# ArduiNode.net
KiCad netlist of a schematic drawn in EAGLE
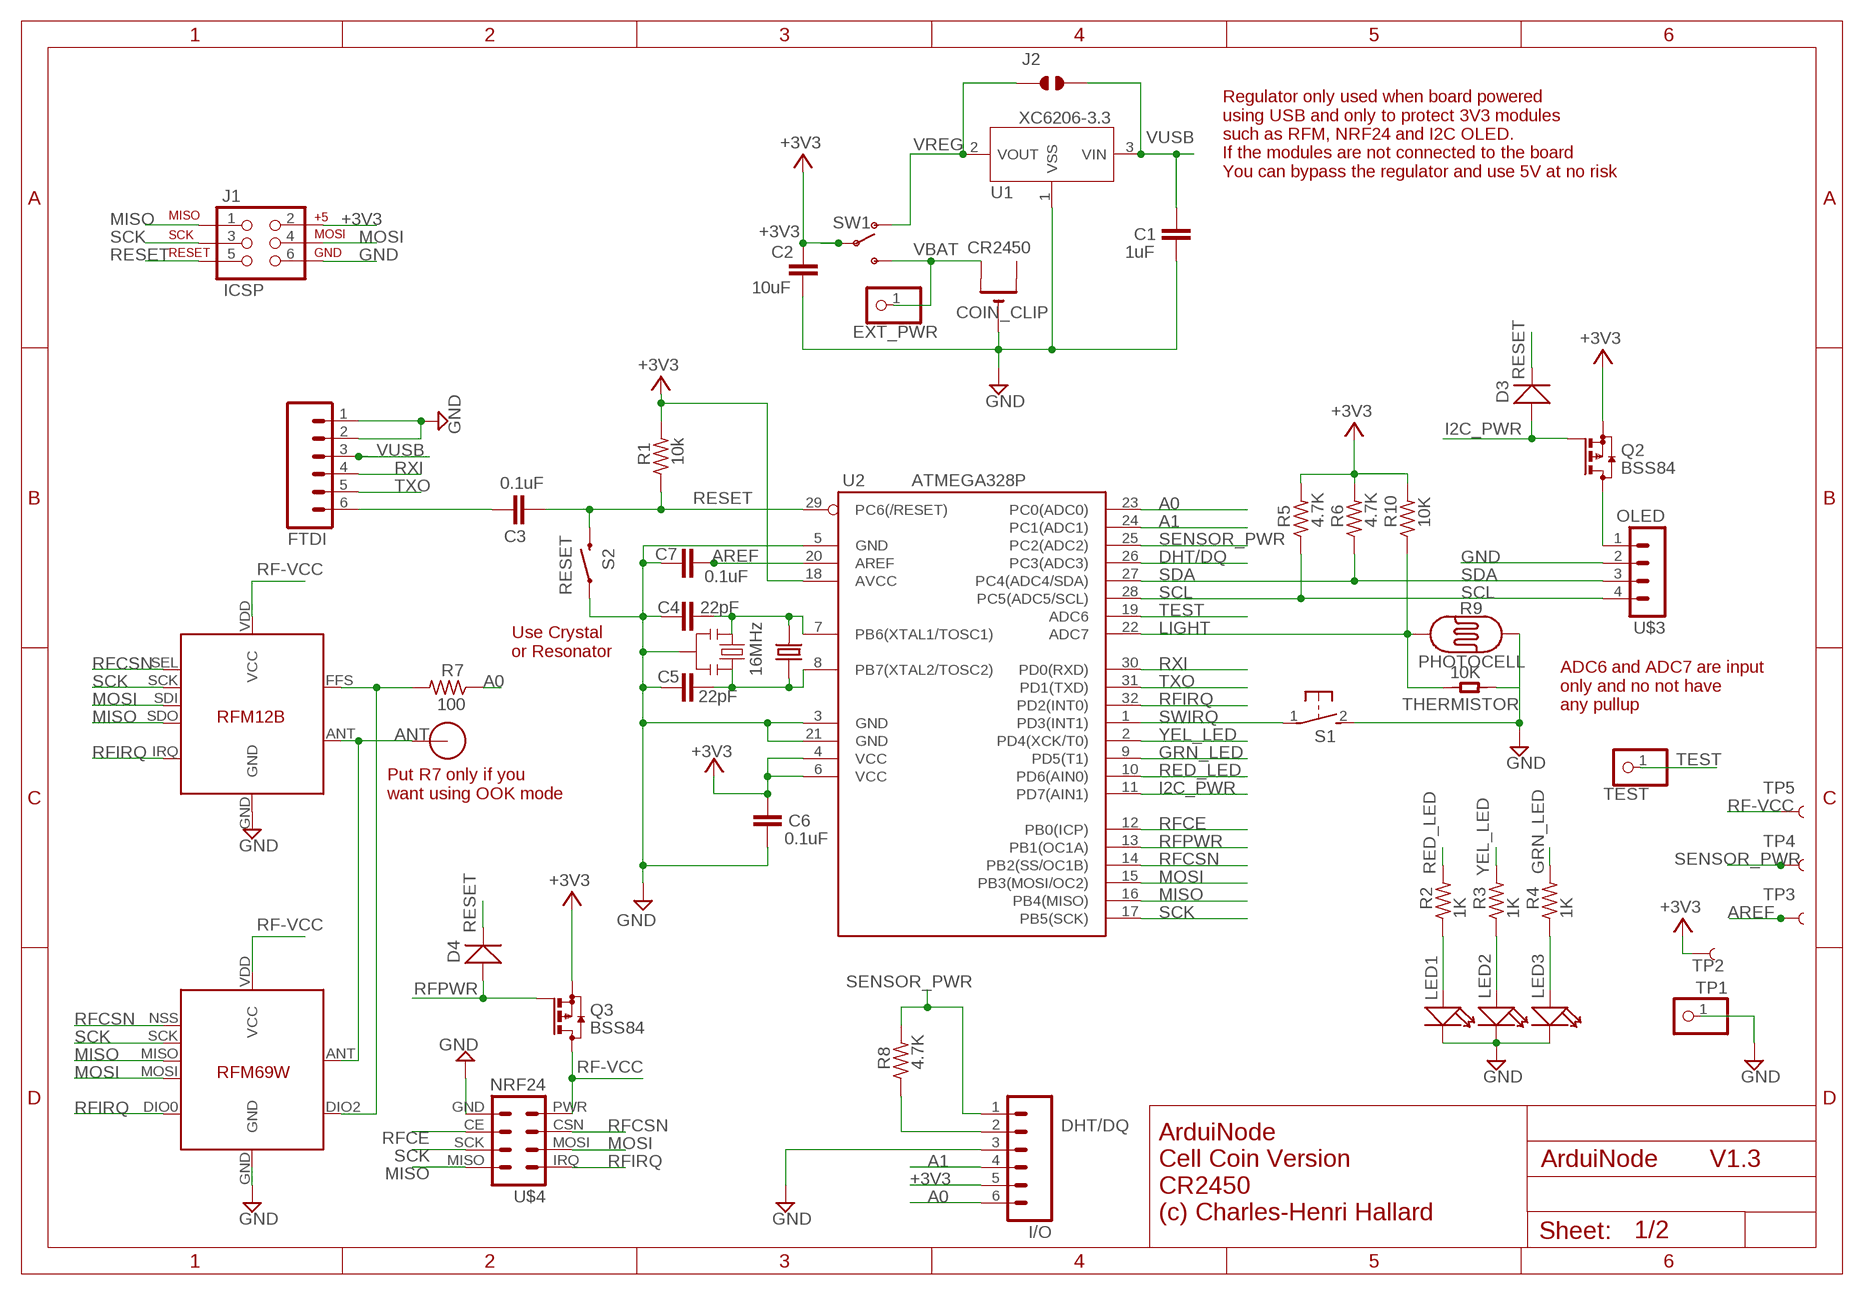
[diagram p0: schematic, sheet 1]
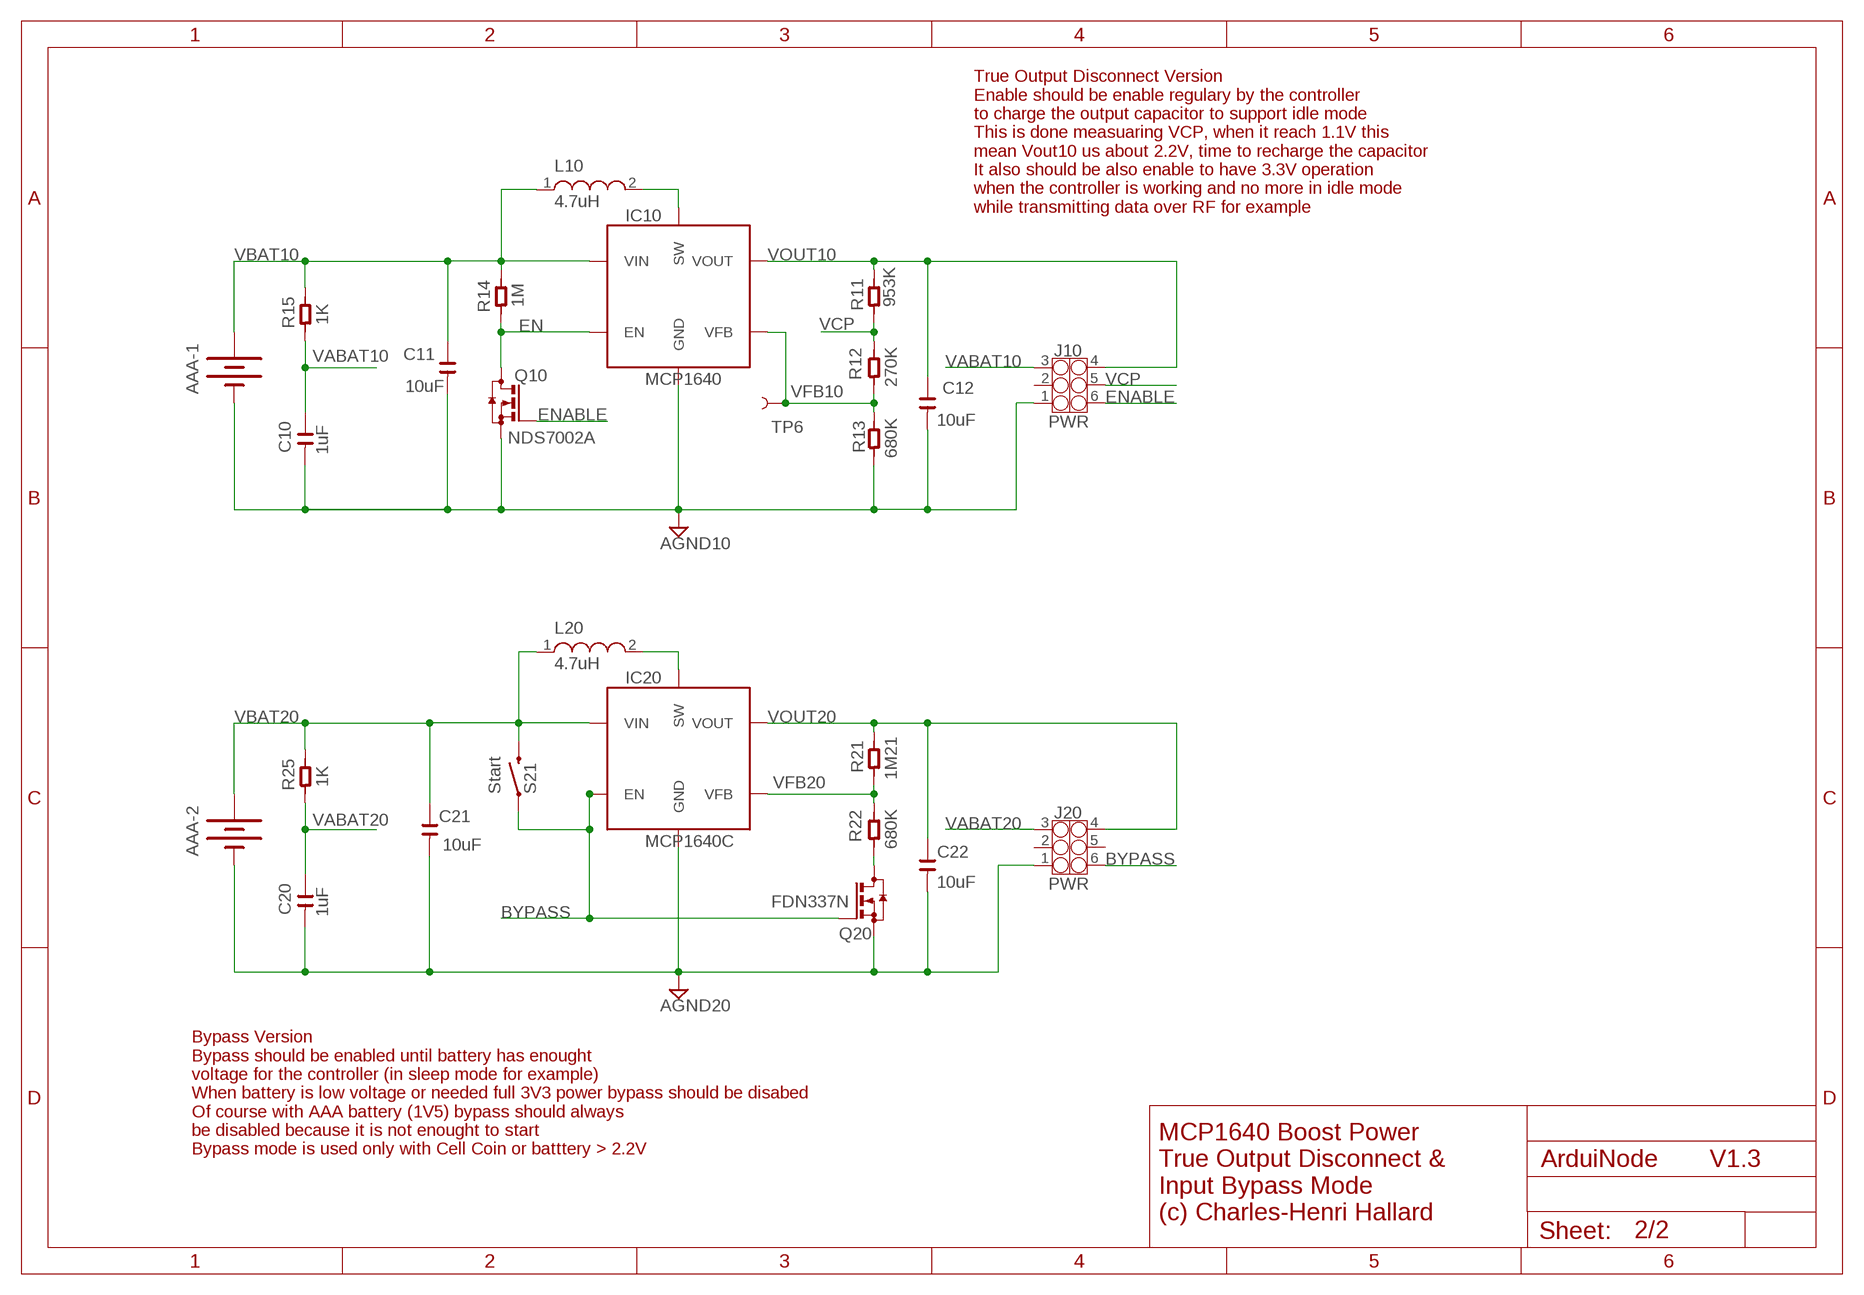
[diagram p1: schematic, sheet 2]

(export (version "E")
  (design (tool "Eeschema 10.0.6"))
  (components
    (comp (ref "AAA-1")
      (value "BATTERYAAA-JL")
      (footprint "eagle-import:BATTERY-AAA-JL")
      (libsource (lib "eagle-import") (part "BATTERYAAA-JL"))
    )
    (comp (ref "AAA-2")
      (value "BATTERYAAA-JL")
      (footprint "eagle-import:BATTERY-AAA-JL")
      (libsource (lib "eagle-import") (part "BATTERYAAA-JL"))
    )
    (comp (ref "C10")
      (value "1uF")
      (footprint "eagle-import:C0805")
      (libsource (lib "eagle-import") (part "C-0805"))
    )
    (comp (ref "C11")
      (value "10uF")
      (footprint "eagle-import:C0805")
      (libsource (lib "eagle-import") (part "C-0805"))
    )
    (comp (ref "C12")
      (value "10uF")
      (footprint "eagle-import:C0805")
      (libsource (lib "eagle-import") (part "C-0805"))
    )
    (comp (ref "C20")
      (value "1uF")
      (footprint "eagle-import:C0805")
      (libsource (lib "eagle-import") (part "C-0805"))
    )
    (comp (ref "C21")
      (value "10uF")
      (footprint "eagle-import:C0805")
      (libsource (lib "eagle-import") (part "C-0805"))
    )
    (comp (ref "C22")
      (value "10uF")
      (footprint "eagle-import:C0805")
      (libsource (lib "eagle-import") (part "C-0805"))
    )
    (comp (ref "IC10")
      (value "MCP1640")
      (footprint "eagle-import:SOT23-6")
      (libsource (lib "eagle-import") (part "MCP1640"))
    )
    (comp (ref "IC20")
      (value "MCP1640C")
      (footprint "eagle-import:SOT23-6")
      (libsource (lib "eagle-import") (part "MCP1640"))
    )
    (comp (ref "J10")
      (value "PWR")
      (footprint "eagle-import:2X3P-2.54-2.54-11.6-3.0-BLACK-MALE")
      (libsource (lib "eagle-import") (part "CONNECTOR-HEADER-2X3P-3460180P1"))
    )
    (comp (ref "J20")
      (value "PWR")
      (footprint "eagle-import:2X3P-2.54-2.54-11.6-3.0-BLACK-MALE")
      (libsource (lib "eagle-import") (part "CONNECTOR-HEADER-2X3P-3460180P1"))
    )
    (comp (ref "L10")
      (value "4.7uH")
      (footprint "eagle-import:L1812")
      (libsource (lib "eagle-import") (part "INDUCTOR-L1812"))
    )
    (comp (ref "L20")
      (value "4.7uH")
      (footprint "eagle-import:L1812")
      (libsource (lib "eagle-import") (part "INDUCTOR-L1812"))
    )
    (comp (ref "Q10")
      (value "NDS7002A")
      (footprint "eagle-import:SOT23")
      (libsource (lib "eagle-import") (part "BSS123"))
    )
    (comp (ref "Q20")
      (value "FDN337N")
      (footprint "eagle-import:SOT23")
      (libsource (lib "eagle-import") (part "BSS123"))
    )
    (comp (ref "R11")
      (value "953K")
      (footprint "eagle-import:R0603")
      (libsource (lib "eagle-import") (part "R-0603"))
    )
    (comp (ref "R12")
      (value "270K")
      (footprint "eagle-import:R0603")
      (libsource (lib "eagle-import") (part "R-0603"))
    )
    (comp (ref "R13")
      (value "680K")
      (footprint "eagle-import:R0603")
      (libsource (lib "eagle-import") (part "R-0603"))
    )
    (comp (ref "R14")
      (value "1M")
      (footprint "eagle-import:R0603")
      (libsource (lib "eagle-import") (part "R-0603"))
    )
    (comp (ref "R15")
      (value "1K")
      (footprint "eagle-import:R0603")
      (libsource (lib "eagle-import") (part "R-0603"))
    )
    (comp (ref "R21")
      (value "1M21")
      (footprint "eagle-import:R0603")
      (libsource (lib "eagle-import") (part "R-0603"))
    )
    (comp (ref "R22")
      (value "680K")
      (footprint "eagle-import:R0603")
      (libsource (lib "eagle-import") (part "R-0603"))
    )
    (comp (ref "R25")
      (value "1K")
      (footprint "eagle-import:R0603")
      (libsource (lib "eagle-import") (part "R-0603"))
    )
    (comp (ref "S21")
      (value "Start")
      (footprint "eagle-import:TACTILE-SWITCH-1101NE")
      (libsource (lib "eagle-import") (part "SWITCH-MOMENTARY-2-SMD-1101NE"))
    )
    (comp (ref "TP6")
      (value "TEST-POINT3")
      (footprint "eagle-import:PAD.03X.03")
      (libsource (lib "eagle-import") (part "TEST-POINT3"))
    )
    (comp (ref "C1")
      (value "1uF")
      (footprint "eagle-import:C0805K")
      (libsource (lib "eagle-import") (part "C-EUC0805K"))
    )
    (comp (ref "C2")
      (value "10uF")
      (footprint "eagle-import:C0805K")
      (libsource (lib "eagle-import") (part "C-EUC0805K"))
    )
    (comp (ref "C3")
      (value "0.1uF")
      (footprint "eagle-import:C0805K")
      (libsource (lib "eagle-import") (part "C-EUC0805K"))
    )
    (comp (ref "C4")
      (value "22pF")
      (footprint "eagle-import:C0805K")
      (libsource (lib "eagle-import") (part "C-EUC0805K"))
    )
    (comp (ref "C5")
      (value "22pF")
      (footprint "eagle-import:C0805K")
      (libsource (lib "eagle-import") (part "C-EUC0805K"))
    )
    (comp (ref "C6")
      (value "0.1uF")
      (footprint "eagle-import:C0805K")
      (libsource (lib "eagle-import") (part "C-EUC0805K"))
    )
    (comp (ref "C7")
      (value "0.1uF")
      (footprint "eagle-import:C0805K")
      (libsource (lib "eagle-import") (part "C-EUC0805K"))
    )
    (comp (ref "COIN_CLIP")
      (value "CR2450")
      (footprint "eagle-import:CR1220-THM")
      (libsource (lib "eagle-import") (part "CR2450CR2450-THM"))
    )
    (comp (ref "D3")
      (value "D-SOD-123")
      (footprint "eagle-import:SOD123")
      (libsource (lib "eagle-import") (part "D-SOD-123"))
    )
    (comp (ref "D4")
      (value "D-SOD-123")
      (footprint "eagle-import:SOD123")
      (libsource (lib "eagle-import") (part "D-SOD-123"))
    )
    (comp (ref "EXT_PWR")
      (value "PINHD-1X1CB")
      (footprint "eagle-import:1X01-CLEANBIG")
      (libsource (lib "eagle-import") (part "PINHD-1X1CB"))
    )
    (comp (ref "FTDI")
      (value "M06SIP_LOCK")
      (footprint "eagle-import:1X06-SIP_LOCK")
      (libsource (lib "eagle-import") (part "M06SIP_LOCK"))
    )
    (comp (ref "I/O")
      (value "M06FEMALE_LOCK")
      (footprint "eagle-import:1X06_FEMALE_LOCK.010")
      (libsource (lib "eagle-import") (part "M06FEMALE_LOCK"))
    )
    (comp (ref "J1")
      (value "ICSP")
      (footprint "eagle-import:2X3_LOCK")
      (libsource (lib "eagle-import") (part "AVR_SPI_PRG_62X3_LOCK"))
    )
    (comp (ref "J2")
      (value "JUMPER_SOLDER_1X2")
      (footprint "eagle-import:JUMPER_SOLDER_1X2")
      (libsource (lib "eagle-import") (part "JUMPER_SOLDER_1X2"))
    )
    (comp (ref "LED1")
      (value "LED0805")
      (footprint "eagle-import:LED-0805")
      (libsource (lib "eagle-import") (part "LED0805"))
    )
    (comp (ref "LED2")
      (value "LED0805")
      (footprint "eagle-import:LED-0805")
      (libsource (lib "eagle-import") (part "LED0805"))
    )
    (comp (ref "LED3")
      (value "LED0805")
      (footprint "eagle-import:LED-0805")
      (libsource (lib "eagle-import") (part "LED0805"))
    )
    (comp (ref "Q2")
      (value "BSS84")
      (footprint "eagle-import:SOT23")
      (libsource (lib "eagle-import") (part "BSS84"))
    )
    (comp (ref "Q3")
      (value "BSS84")
      (footprint "eagle-import:SOT23")
      (libsource (lib "eagle-import") (part "BSS84"))
    )
    (comp (ref "R1")
      (value "10k")
      (footprint "eagle-import:M0805")
      (libsource (lib "eagle-import") (part "R-US_M0805"))
    )
    (comp (ref "R2")
      (value "1K")
      (footprint "eagle-import:M0805")
      (libsource (lib "eagle-import") (part "R-US_M0805"))
    )
    (comp (ref "R3")
      (value "1K")
      (footprint "eagle-import:M0805")
      (libsource (lib "eagle-import") (part "R-US_M0805"))
    )
    (comp (ref "R4")
      (value "1K")
      (footprint "eagle-import:M0805")
      (libsource (lib "eagle-import") (part "R-US_M0805"))
    )
    (comp (ref "R5")
      (value "4.7K")
      (footprint "eagle-import:M0805")
      (libsource (lib "eagle-import") (part "R-US_M0805"))
    )
    (comp (ref "R6")
      (value "4.7K")
      (footprint "eagle-import:M0805")
      (libsource (lib "eagle-import") (part "R-US_M0805"))
    )
    (comp (ref "R7")
      (value "100")
      (footprint "eagle-import:M0805")
      (libsource (lib "eagle-import") (part "R-US_M0805"))
    )
    (comp (ref "R8")
      (value "4.7K")
      (footprint "eagle-import:M0805")
      (libsource (lib "eagle-import") (part "R-US_M0805"))
    )
    (comp (ref "R9")
      (value "PHOTOCELL")
      (footprint "eagle-import:PHOTOCELL")
      (libsource (lib "eagle-import") (part "PHOTOCELLPTH"))
    )
    (comp (ref "R10")
      (value "10K")
      (footprint "eagle-import:M0805")
      (libsource (lib "eagle-import") (part "R-US_M0805"))
    )
    (comp (ref "RFM12B")
      (value "RFM12BNO")
      (footprint "eagle-import:RFM12B")
      (libsource (lib "eagle-import") (part "RFM12BNO"))
    )
    (comp (ref "S1")
      (value "DTS-3")
      (footprint "eagle-import:DTS-3")
      (libsource (lib "eagle-import") (part "DTS-3"))
    )
    (comp (ref "S2")
      (value "RESET")
      (footprint "eagle-import:TACTILE-SWITCH-1101NE")
      (libsource (lib "eagle-import") (part "SWITCH-MOMENTARY-2-SMD-1101NE"))
    )
    (comp (ref "SW1")
      (value "USB_COIN")
      (footprint "eagle-import:SWITCH-SPDT-SMD")
      (libsource (lib "eagle-import") (part "SW_SPDT_SMD"))
    )
    (comp (ref "TEST")
      (value "PINHD-1X1CB")
      (footprint "eagle-import:1X01-CLEANBIG")
      (libsource (lib "eagle-import") (part "PINHD-1X1CB"))
    )
    (comp (ref "THERMISTOR")
      (value "10K")
      (footprint "eagle-import:R0603")
      (libsource (lib "eagle-import") (part "R-0603"))
    )
    (comp (ref "TP1")
      (value "PINHD-1X1")
      (footprint "eagle-import:1X01")
      (libsource (lib "eagle-import") (part "PINHD-1X1"))
    )
    (comp (ref "TP2")
      (value "TEST-POINT3X5")
      (footprint "eagle-import:PAD.03X.05")
      (libsource (lib "eagle-import") (part "TEST-POINT3X5"))
    )
    (comp (ref "TP3")
      (value "TEST-POINT3X5")
      (footprint "eagle-import:PAD.03X.05")
      (libsource (lib "eagle-import") (part "TEST-POINT3X5"))
    )
    (comp (ref "TP4")
      (value "TEST-POINT3X5")
      (footprint "eagle-import:PAD.03X.05")
      (libsource (lib "eagle-import") (part "TEST-POINT3X5"))
    )
    (comp (ref "TP5")
      (value "TEST-POINT3X5")
      (footprint "eagle-import:PAD.03X.05")
      (libsource (lib "eagle-import") (part "TEST-POINT3X5"))
    )
    (comp (ref "U$3")
      (value "OLED")
      (footprint "eagle-import:1X04_LOCK")
      (libsource (lib "eagle-import") (part "M04_LOCK"))
    )
    (comp (ref "U$4")
      (value "NRF24")
      (footprint "eagle-import:2X04_LOCK")
      (libsource (lib "eagle-import") (part "NRF24"))
    )
    (comp (ref "U$11")
      (value "RFM12B_ANTENNA")
      (footprint "eagle-import:RFM12B-ANTENNA")
      (libsource (lib "eagle-import") (part "RFM12B_ANTENNA"))
    )
    (comp (ref "U1")
      (value "XC6206-3.3")
      (footprint "eagle-import:SOT23")
      (libsource (lib "eagle-import") (part "XC6206-3.3-1300260P1"))
    )
    (comp (ref "U2")
      (value "ATMEGA328P")
      (footprint "eagle-import:TQFP32")
      (libsource (lib "eagle-import") (part "ATMEGA328P-AU-1030060P1"))
    )
    (comp (ref "X2")
      (value "16MHz")
      (footprint "eagle-import:2P-SMD-5.0X3.2")
      (libsource (lib "eagle-import") (part "CRYSTAL-0500290P1"))
    )
    (comp (ref "X3")
      (value "RFM69")
      (footprint "eagle-import:RFM69W-MINPADS")
      (libsource (lib "eagle-import") (part "RFM69"))
    )
    (comp (ref "Y1")
      (value "16MHz")
      (footprint "eagle-import:RESONATOR-SMD")
      (libsource (lib "eagle-import") (part "RESONATOR16MHZ"))
    )
  )
  (nets
    (net (code "1") (name "+3V3") (class "Default")
      (node (ref "C2") (pin "1") (pinfunction "1_1") (pintype "passive"))
      (node (ref "C6") (pin "2") (pinfunction "2_2") (pintype "passive"))
      (node (ref "I/O") (pin "5") (pinfunction "5_5") (pintype "passive"))
      (node (ref "J1") (pin "2") (pinfunction "2_2") (pintype "passive"))
      (node (ref "Q2") (pin "2") (pinfunction "S_2") (pintype "passive"))
      (node (ref "Q3") (pin "2") (pinfunction "S_2") (pintype "passive"))
      (node (ref "R1") (pin "2") (pinfunction "2_2") (pintype "passive"))
      (node (ref "R10") (pin "2") (pinfunction "2_2") (pintype "passive"))
      (node (ref "R5") (pin "2") (pinfunction "2_2") (pintype "passive"))
      (node (ref "R6") (pin "2") (pinfunction "2_2") (pintype "passive"))
      (node (ref "SW1") (pin "2") (pinfunction "2_2") (pintype "passive"))
      (node (ref "TP2") (pin "P$1") (pinfunction "1_P$1") (pintype "bidirectional"))
      (node (ref "U2") (pin "18") (pinfunction "AVCC_18") (pintype "bidirectional"))
      (node (ref "U2") (pin "4") (pinfunction "VCC_4") (pintype "bidirectional"))
      (node (ref "U2") (pin "6") (pinfunction "VCC_6") (pintype "bidirectional"))
    )
    (net (code "2") (name "A0") (class "Default")
      (node (ref "I/O") (pin "6") (pinfunction "6_6") (pintype "passive"))
      (node (ref "R7") (pin "1") (pinfunction "1_1") (pintype "passive"))
      (node (ref "U2") (pin "23") (pinfunction "PC0(ADC0)_23") (pintype "bidirectional"))
    )
    (net (code "3") (name "A1") (class "Default")
      (node (ref "I/O") (pin "4") (pinfunction "4_4") (pintype "passive"))
      (node (ref "U2") (pin "24") (pinfunction "PC1(ADC1)_24") (pintype "bidirectional"))
    )
    (net (code "4") (name "AGND10") (class "Default")
      (node (ref "AAA-1") (pin "GND@1") (pinfunction "-_GND@1") (pintype "power_in"))
      (node (ref "C10") (pin "1") (pinfunction "1_1") (pintype "bidirectional"))
      (node (ref "C11") (pin "1") (pinfunction "1_1") (pintype "bidirectional"))
      (node (ref "C12") (pin "1") (pinfunction "1_1") (pintype "bidirectional"))
      (node (ref "IC10") (pin "2") (pinfunction "GND_2") (pintype "power_in"))
      (node (ref "J10") (pin "1") (pinfunction "1_1") (pintype "bidirectional"))
      (node (ref "Q10") (pin "2") (pinfunction "S_2") (pintype "passive"))
      (node (ref "R13") (pin "1") (pinfunction "1_1") (pintype "bidirectional"))
    )
    (net (code "5") (name "AGND20") (class "Default")
      (node (ref "AAA-2") (pin "GND@1") (pinfunction "-_GND@1") (pintype "power_in"))
      (node (ref "C20") (pin "1") (pinfunction "1_1") (pintype "bidirectional"))
      (node (ref "C21") (pin "1") (pinfunction "1_1") (pintype "bidirectional"))
      (node (ref "C22") (pin "1") (pinfunction "1_1") (pintype "bidirectional"))
      (node (ref "IC20") (pin "2") (pinfunction "GND_2") (pintype "power_in"))
      (node (ref "J20") (pin "1") (pinfunction "1_1") (pintype "bidirectional"))
      (node (ref "Q20") (pin "2") (pinfunction "S_2") (pintype "passive"))
    )
    (net (code "6") (name "ANT") (class "Default")
      (node (ref "RFM12B") (pin "ANT") (pinfunction "ANT_ANT") (pintype "passive"))
      (node (ref "U$11") (pin "P$1") (pinfunction "1_P$1") (pintype "bidirectional"))
      (node (ref "X3") (pin "ANT") (pinfunction "ANT_ANT") (pintype "passive"))
    )
    (net (code "7") (name "AREF") (class "Default")
      (node (ref "C7") (pin "1") (pinfunction "1_1") (pintype "passive"))
      (node (ref "TP3") (pin "P$1") (pinfunction "1_P$1") (pintype "bidirectional"))
      (node (ref "U2") (pin "20") (pinfunction "AREF_20") (pintype "bidirectional"))
    )
    (net (code "8") (name "BYPASS") (class "Default")
      (node (ref "IC20") (pin "3") (pinfunction "EN_3") (pintype "input"))
      (node (ref "J20") (pin "6") (pinfunction "6_6") (pintype "bidirectional"))
      (node (ref "Q20") (pin "1") (pinfunction "G_1") (pintype "passive"))
      (node (ref "S21") (pin "P$1") (pinfunction "1_P$1") (pintype "passive"))
    )
    (net (code "9") (name "DHT{slash}DQ") (class "Default")
      (node (ref "I/O") (pin "2") (pinfunction "2_2") (pintype "passive"))
      (node (ref "R8") (pin "1") (pinfunction "1_1") (pintype "passive"))
      (node (ref "U2") (pin "26") (pinfunction "PC3(ADC3)_26") (pintype "bidirectional"))
    )
    (net (code "10") (name "EN") (class "Default")
      (node (ref "IC10") (pin "3") (pinfunction "EN_3") (pintype "input"))
      (node (ref "Q10") (pin "3") (pinfunction "D_3") (pintype "passive"))
      (node (ref "R14") (pin "1") (pinfunction "1_1") (pintype "bidirectional"))
    )
    (net (code "11") (name "ENABLE") (class "Default")
      (node (ref "J10") (pin "6") (pinfunction "6_6") (pintype "bidirectional"))
      (node (ref "Q10") (pin "1") (pinfunction "G_1") (pintype "passive"))
    )
    (net (code "12") (name "GND") (class "Default")
      (node (ref "C1") (pin "2") (pinfunction "2_2") (pintype "passive"))
      (node (ref "C2") (pin "2") (pinfunction "2_2") (pintype "passive"))
      (node (ref "C4") (pin "2") (pinfunction "2_2") (pintype "passive"))
      (node (ref "C5") (pin "2") (pinfunction "2_2") (pintype "passive"))
      (node (ref "C6") (pin "1") (pinfunction "1_1") (pintype "passive"))
      (node (ref "C7") (pin "2") (pinfunction "2_2") (pintype "passive"))
      (node (ref "COIN_CLIP") (pin "GND") (pinfunction "-_GND") (pintype "passive"))
      (node (ref "FTDI") (pin "1") (pinfunction "1_1") (pintype "passive"))
      (node (ref "FTDI") (pin "2") (pinfunction "2_2") (pintype "passive"))
      (node (ref "I/O") (pin "3") (pinfunction "3_3") (pintype "passive"))
      (node (ref "J1") (pin "6") (pinfunction "6_6") (pintype "passive"))
      (node (ref "LED1") (pin "-") (pinfunction "-_-") (pintype "passive"))
      (node (ref "LED2") (pin "-") (pinfunction "-_-") (pintype "passive"))
      (node (ref "LED3") (pin "-") (pinfunction "-_-") (pintype "passive"))
      (node (ref "R9") (pin "1") (pinfunction "P$1_1") (pintype "bidirectional"))
      (node (ref "RFM12B") (pin "GND") (pinfunction "GND_GND") (pintype "power_in"))
      (node (ref "S1") (pin "2") (pinfunction "2_2") (pintype "passive"))
      (node (ref "S2") (pin "P$1") (pinfunction "1_P$1") (pintype "passive"))
      (node (ref "THERMISTOR") (pin "1") (pinfunction "1_1") (pintype "bidirectional"))
      (node (ref "TP1") (pin "1") (pinfunction "1_1") (pintype "passive"))
      (node (ref "U$3") (pin "2") (pinfunction "2_2") (pintype "passive"))
      (node (ref "U$4") (pin "GND") (pinfunction "GND_GND") (pintype "power_in"))
      (node (ref "U1") (pin "1") (pinfunction "VSS_1") (pintype "power_in"))
      (node (ref "U2") (pin "21") (pinfunction "GND_21") (pintype "bidirectional"))
      (node (ref "U2") (pin "3") (pinfunction "GND_3") (pintype "bidirectional"))
      (node (ref "U2") (pin "5") (pinfunction "GND_5") (pintype "bidirectional"))
      (node (ref "X3") (pin "GND") (pinfunction "GND_GND") (pintype "power_in"))
      (node (ref "Y1") (pin "2") (pinfunction "2_2") (pintype "passive"))
    )
    (net (code "13") (name "GRN_LED") (class "Default")
      (node (ref "R4") (pin "2") (pinfunction "2_2") (pintype "passive"))
      (node (ref "U2") (pin "9") (pinfunction "PD5(T1)_9") (pintype "bidirectional"))
    )
    (net (code "14") (name "I2C_PWR") (class "Default")
      (node (ref "D3") (pin "+") (pinfunction "+_+") (pintype "passive"))
      (node (ref "Q2") (pin "1") (pinfunction "G_1") (pintype "passive"))
      (node (ref "U2") (pin "11") (pinfunction "PD7(AIN1)_11") (pintype "bidirectional"))
    )
    (net (code "15") (name "LIGHT") (class "Default")
      (node (ref "R10") (pin "1") (pinfunction "1_1") (pintype "passive"))
      (node (ref "R9") (pin "2") (pinfunction "P$2_2") (pintype "bidirectional"))
      (node (ref "THERMISTOR") (pin "2") (pinfunction "2_2") (pintype "bidirectional"))
      (node (ref "U2") (pin "22") (pinfunction "ADC7_22") (pintype "bidirectional"))
    )
    (net (code "16") (name "MISO") (class "Default")
      (node (ref "J1") (pin "1") (pinfunction "1_1") (pintype "passive"))
      (node (ref "RFM12B") (pin "SDO") (pinfunction "SDO_SDO") (pintype "output"))
      (node (ref "U$4") (pin "MISO") (pinfunction "MISO_MISO") (pintype "passive"))
      (node (ref "U2") (pin "16") (pinfunction "PB4(MISO)_16") (pintype "bidirectional"))
      (node (ref "X3") (pin "MISO") (pinfunction "MISO_MISO") (pintype "input"))
    )
    (net (code "17") (name "MOSI") (class "Default")
      (node (ref "J1") (pin "4") (pinfunction "4_4") (pintype "passive"))
      (node (ref "RFM12B") (pin "SDI") (pinfunction "SDI_SDI") (pintype "input"))
      (node (ref "U$4") (pin "MOSI") (pinfunction "MOSI_MOSI") (pintype "passive"))
      (node (ref "U2") (pin "15") (pinfunction "PB3(MOSI/OC2)_15") (pintype "bidirectional"))
      (node (ref "X3") (pin "MOSI") (pinfunction "MOSI_MOSI") (pintype "output"))
    )
    (net (code "18") (name "Net-(C3-Pad1)") (class "Default")
      (node (ref "C3") (pin "1") (pinfunction "1_1") (pintype "passive"))
      (node (ref "FTDI") (pin "6") (pinfunction "6_6") (pintype "passive"))
    )
    (net (code "19") (name "Net-(IC10-SW)") (class "Default")
      (node (ref "IC10") (pin "1") (pinfunction "SW_1") (pintype "passive"))
      (node (ref "L10") (pin "2") (pinfunction "2_2") (pintype "passive"))
    )
    (net (code "20") (name "Net-(IC20-SW)") (class "Default")
      (node (ref "IC20") (pin "1") (pinfunction "SW_1") (pintype "passive"))
      (node (ref "L20") (pin "2") (pinfunction "2_2") (pintype "passive"))
    )
    (net (code "21") (name "Net-(LED1-Pad+)") (class "Default")
      (node (ref "LED1") (pin "+") (pinfunction "+_+") (pintype "passive"))
      (node (ref "R2") (pin "1") (pinfunction "1_1") (pintype "passive"))
    )
    (net (code "22") (name "Net-(LED2-Pad+)") (class "Default")
      (node (ref "LED2") (pin "+") (pinfunction "+_+") (pintype "passive"))
      (node (ref "R3") (pin "1") (pinfunction "1_1") (pintype "passive"))
    )
    (net (code "23") (name "Net-(LED3-Pad+)") (class "Default")
      (node (ref "LED3") (pin "+") (pinfunction "+_+") (pintype "passive"))
      (node (ref "R4") (pin "1") (pinfunction "1_1") (pintype "passive"))
    )
    (net (code "24") (name "Net-(Q2-D)") (class "Default")
      (node (ref "Q2") (pin "3") (pinfunction "D_3") (pintype "passive"))
      (node (ref "U$3") (pin "1") (pinfunction "1_1") (pintype "passive"))
    )
    (net (code "25") (name "Net-(Q20-D)") (class "Default")
      (node (ref "Q20") (pin "3") (pinfunction "D_3") (pintype "passive"))
      (node (ref "R22") (pin "1") (pinfunction "1_1") (pintype "bidirectional"))
    )
    (net (code "26") (name "Net-(R7-Pad2)") (class "Default")
      (node (ref "R7") (pin "2") (pinfunction "2_2") (pintype "passive"))
      (node (ref "RFM12B") (pin "FFS") (pinfunction "FFS_FFS") (pintype "bidirectional"))
      (node (ref "X3") (pin "DIO2") (pinfunction "DIO2_DIO2") (pintype "open_collector"))
    )
    (net (code "27") (name "Net-(U2-PB6(XTAL1{slash}TOSC1))") (class "Default")
      (node (ref "C4") (pin "1") (pinfunction "1_1") (pintype "passive"))
      (node (ref "U2") (pin "7") (pinfunction "PB6(XTAL1/TOSC1)_7") (pintype "bidirectional"))
      (node (ref "X2") (pin "2") (pinfunction "2_2") (pintype "passive"))
      (node (ref "Y1") (pin "1") (pinfunction "1_1") (pintype "passive"))
    )
    (net (code "28") (name "Net-(U2-PB7(XTAL2{slash}TOSC2))") (class "Default")
      (node (ref "C5") (pin "1") (pinfunction "1_1") (pintype "passive"))
      (node (ref "U2") (pin "8") (pinfunction "PB7(XTAL2/TOSC2)_8") (pintype "bidirectional"))
      (node (ref "X2") (pin "1") (pinfunction "1_1") (pintype "passive"))
      (node (ref "Y1") (pin "3") (pinfunction "3_3") (pintype "passive"))
    )
    (net (code "29") (name "RED_LED") (class "Default")
      (node (ref "R2") (pin "2") (pinfunction "2_2") (pintype "passive"))
      (node (ref "U2") (pin "10") (pinfunction "PD6(AIN0)_10") (pintype "bidirectional"))
    )
    (net (code "30") (name "RESET") (class "Default")
      (node (ref "C3") (pin "2") (pinfunction "2_2") (pintype "passive"))
      (node (ref "D3") (pin "-") (pinfunction "-_-") (pintype "passive"))
      (node (ref "D4") (pin "-") (pinfunction "-_-") (pintype "passive"))
      (node (ref "J1") (pin "5") (pinfunction "5_5") (pintype "passive"))
      (node (ref "R1") (pin "1") (pinfunction "1_1") (pintype "passive"))
      (node (ref "S2") (pin "P$2") (pinfunction "2_P$2") (pintype "passive"))
      (node (ref "U2") (pin "29") (pinfunction "PC6(/RESET)_29") (pintype "bidirectional"))
    )
    (net (code "31") (name "RF-VCC") (class "Default")
      (node (ref "Q3") (pin "3") (pinfunction "D_3") (pintype "passive"))
      (node (ref "RFM12B") (pin "VDD") (pinfunction "VCC_VDD") (pintype "power_in"))
      (node (ref "TP5") (pin "P$1") (pinfunction "1_P$1") (pintype "bidirectional"))
      (node (ref "U$4") (pin "PWR") (pinfunction "VCC_PWR") (pintype "power_in"))
      (node (ref "X3") (pin "VDD") (pinfunction "VCC_VDD") (pintype "power_in"))
    )
    (net (code "32") (name "RFCE") (class "Default")
      (node (ref "U$4") (pin "CE") (pinfunction "CE_CE") (pintype "passive"))
      (node (ref "U2") (pin "12") (pinfunction "PB0(ICP)_12") (pintype "bidirectional"))
    )
    (net (code "33") (name "RFCSN") (class "Default")
      (node (ref "RFM12B") (pin "SEL") (pinfunction "SEL_SEL") (pintype "input"))
      (node (ref "U$4") (pin "CSN") (pinfunction "CSN_CSN") (pintype "passive"))
      (node (ref "U2") (pin "14") (pinfunction "PB2(SS/OC1B)_14") (pintype "bidirectional"))
      (node (ref "X3") (pin "NSS") (pinfunction "SEL_NSS") (pintype "input"))
    )
    (net (code "34") (name "RFIRQ") (class "Default")
      (node (ref "RFM12B") (pin "IRQ") (pinfunction "IRQ_IRQ") (pintype "open_collector"))
      (node (ref "U$4") (pin "IRQ") (pinfunction "IRQ_IRQ") (pintype "passive"))
      (node (ref "U2") (pin "32") (pinfunction "PD2(INT0)_32") (pintype "bidirectional"))
      (node (ref "X3") (pin "DIO0") (pinfunction "DIO0_DIO0") (pintype "open_collector"))
    )
    (net (code "35") (name "RFPWR") (class "Default")
      (node (ref "D4") (pin "+") (pinfunction "+_+") (pintype "passive"))
      (node (ref "Q3") (pin "1") (pinfunction "G_1") (pintype "passive"))
      (node (ref "U2") (pin "13") (pinfunction "PB1(OC1A)_13") (pintype "bidirectional"))
    )
    (net (code "36") (name "RXI") (class "Default")
      (node (ref "FTDI") (pin "4") (pinfunction "4_4") (pintype "passive"))
      (node (ref "U2") (pin "30") (pinfunction "PD0(RXD)_30") (pintype "bidirectional"))
    )
    (net (code "37") (name "SCK") (class "Default")
      (node (ref "J1") (pin "3") (pinfunction "3_3") (pintype "passive"))
      (node (ref "RFM12B") (pin "SCK") (pinfunction "SCK_SCK") (pintype "input"))
      (node (ref "U$4") (pin "SCK") (pinfunction "CLK_SCK") (pintype "passive"))
      (node (ref "U2") (pin "17") (pinfunction "PB5(SCK)_17") (pintype "bidirectional"))
      (node (ref "X3") (pin "SCK") (pinfunction "SCK_SCK") (pintype "input"))
    )
    (net (code "38") (name "SCL") (class "Default")
      (node (ref "R5") (pin "1") (pinfunction "1_1") (pintype "passive"))
      (node (ref "U$3") (pin "4") (pinfunction "4_4") (pintype "passive"))
      (node (ref "U2") (pin "28") (pinfunction "PC5(ADC5/SCL)_28") (pintype "bidirectional"))
    )
    (net (code "39") (name "SDA") (class "Default")
      (node (ref "R6") (pin "1") (pinfunction "1_1") (pintype "passive"))
      (node (ref "U$3") (pin "3") (pinfunction "3_3") (pintype "passive"))
      (node (ref "U2") (pin "27") (pinfunction "PC4(ADC4/SDA)_27") (pintype "bidirectional"))
    )
    (net (code "40") (name "SENSOR_PWR") (class "Default")
      (node (ref "I/O") (pin "1") (pinfunction "1_1") (pintype "passive"))
      (node (ref "R8") (pin "2") (pinfunction "2_2") (pintype "passive"))
      (node (ref "TP4") (pin "P$1") (pinfunction "1_P$1") (pintype "bidirectional"))
      (node (ref "U2") (pin "25") (pinfunction "PC2(ADC2)_25") (pintype "bidirectional"))
    )
    (net (code "41") (name "SWIRQ") (class "Default")
      (node (ref "S1") (pin "1") (pinfunction "1_1") (pintype "passive"))
      (node (ref "U2") (pin "1") (pinfunction "PD3(INT1)_1") (pintype "bidirectional"))
    )
    (net (code "42") (name "TEST") (class "Default")
      (node (ref "TEST") (pin "1") (pinfunction "1_1") (pintype "passive"))
      (node (ref "U2") (pin "19") (pinfunction "ADC6_19") (pintype "bidirectional"))
    )
    (net (code "43") (name "TXO") (class "Default")
      (node (ref "FTDI") (pin "5") (pinfunction "5_5") (pintype "passive"))
      (node (ref "U2") (pin "31") (pinfunction "PD1(TXD)_31") (pintype "bidirectional"))
    )
    (net (code "44") (name "VABAT10") (class "Default")
      (node (ref "C10") (pin "2") (pinfunction "2_2") (pintype "bidirectional"))
      (node (ref "J10") (pin "3") (pinfunction "3_3") (pintype "bidirectional"))
      (node (ref "R15") (pin "1") (pinfunction "1_1") (pintype "bidirectional"))
    )
    (net (code "45") (name "VABAT20") (class "Default")
      (node (ref "C20") (pin "2") (pinfunction "2_2") (pintype "bidirectional"))
      (node (ref "J20") (pin "3") (pinfunction "3_3") (pintype "bidirectional"))
      (node (ref "R25") (pin "1") (pinfunction "1_1") (pintype "bidirectional"))
    )
    (net (code "46") (name "VBAT") (class "Default")
      (node (ref "COIN_CLIP") (pin "+1") (pinfunction "+_+1") (pintype "passive"))
      (node (ref "EXT_PWR") (pin "1") (pinfunction "1_1") (pintype "passive"))
      (node (ref "SW1") (pin "1") (pinfunction "1_1") (pintype "passive"))
    )
    (net (code "47") (name "VBAT10") (class "Default")
      (node (ref "AAA-1") (pin "PWR@1") (pinfunction "+_PWR@1") (pintype "power_in"))
      (node (ref "C11") (pin "2") (pinfunction "2_2") (pintype "bidirectional"))
      (node (ref "IC10") (pin "6") (pinfunction "VIN_6") (pintype "input"))
      (node (ref "L10") (pin "1") (pinfunction "1_1") (pintype "passive"))
      (node (ref "R14") (pin "2") (pinfunction "2_2") (pintype "bidirectional"))
      (node (ref "R15") (pin "2") (pinfunction "2_2") (pintype "bidirectional"))
    )
    (net (code "48") (name "VBAT20") (class "Default")
      (node (ref "AAA-2") (pin "PWR@1") (pinfunction "+_PWR@1") (pintype "power_in"))
      (node (ref "C21") (pin "2") (pinfunction "2_2") (pintype "bidirectional"))
      (node (ref "IC20") (pin "6") (pinfunction "VIN_6") (pintype "input"))
      (node (ref "L20") (pin "1") (pinfunction "1_1") (pintype "passive"))
      (node (ref "R25") (pin "2") (pinfunction "2_2") (pintype "bidirectional"))
      (node (ref "S21") (pin "P$2") (pinfunction "2_P$2") (pintype "passive"))
    )
    (net (code "49") (name "VCP") (class "Default")
      (node (ref "J10") (pin "5") (pinfunction "5_5") (pintype "bidirectional"))
      (node (ref "R11") (pin "1") (pinfunction "1_1") (pintype "bidirectional"))
      (node (ref "R12") (pin "2") (pinfunction "2_2") (pintype "bidirectional"))
    )
    (net (code "50") (name "VFB10") (class "Default")
      (node (ref "IC10") (pin "4") (pinfunction "VFB_4") (pintype "input"))
      (node (ref "R12") (pin "1") (pinfunction "1_1") (pintype "bidirectional"))
      (node (ref "R13") (pin "2") (pinfunction "2_2") (pintype "bidirectional"))
      (node (ref "TP6") (pin "P$1") (pinfunction "1_P$1") (pintype "bidirectional"))
    )
    (net (code "51") (name "VFB20") (class "Default")
      (node (ref "IC20") (pin "4") (pinfunction "VFB_4") (pintype "input"))
      (node (ref "R21") (pin "1") (pinfunction "1_1") (pintype "bidirectional"))
      (node (ref "R22") (pin "2") (pinfunction "2_2") (pintype "bidirectional"))
    )
    (net (code "52") (name "VOUT10") (class "Default")
      (node (ref "C12") (pin "2") (pinfunction "2_2") (pintype "bidirectional"))
      (node (ref "IC10") (pin "5") (pinfunction "VOUT_5") (pintype "power_in"))
      (node (ref "J10") (pin "4") (pinfunction "4_4") (pintype "bidirectional"))
      (node (ref "R11") (pin "2") (pinfunction "2_2") (pintype "bidirectional"))
    )
    (net (code "53") (name "VOUT20") (class "Default")
      (node (ref "C22") (pin "2") (pinfunction "2_2") (pintype "bidirectional"))
      (node (ref "IC20") (pin "5") (pinfunction "VOUT_5") (pintype "power_in"))
      (node (ref "J20") (pin "4") (pinfunction "4_4") (pintype "bidirectional"))
      (node (ref "R21") (pin "2") (pinfunction "2_2") (pintype "bidirectional"))
    )
    (net (code "54") (name "VREG") (class "Default")
      (node (ref "J2") (pin "1") (pinfunction "1_1") (pintype "passive"))
      (node (ref "SW1") (pin "3") (pinfunction "3_3") (pintype "passive"))
      (node (ref "U1") (pin "2") (pinfunction "VOUT_2") (pintype "output"))
    )
    (net (code "55") (name "VUSB") (class "Default")
      (node (ref "C1") (pin "1") (pinfunction "1_1") (pintype "passive"))
      (node (ref "FTDI") (pin "3") (pinfunction "3_3") (pintype "passive"))
      (node (ref "J2") (pin "2") (pinfunction "2_2") (pintype "passive"))
      (node (ref "U1") (pin "3") (pinfunction "VIN_3") (pintype "input"))
    )
    (net (code "56") (name "YEL_LED") (class "Default")
      (node (ref "R3") (pin "2") (pinfunction "2_2") (pintype "passive"))
      (node (ref "U2") (pin "2") (pinfunction "PD4(XCK/T0)_2") (pintype "bidirectional"))
    )
    (net (code "57") (name "unconnected-(COIN_CLIP-+1-Pad+2)") (class "Default")
      (node (ref "COIN_CLIP") (pin "+2") (pinfunction "+1_+2") (pintype "passive"))
    )
    (net (code "58") (name "unconnected-(J10-Pad2)") (class "Default")
      (node (ref "J10") (pin "2") (pinfunction "2_2") (pintype "bidirectional"))
    )
    (net (code "59") (name "unconnected-(J20-Pad2)") (class "Default")
      (node (ref "J20") (pin "2") (pinfunction "2_2") (pintype "bidirectional"))
    )
    (net (code "60") (name "unconnected-(J20-Pad5)") (class "Default")
      (node (ref "J20") (pin "5") (pinfunction "5_5") (pintype "bidirectional"))
    )
  )
)
